# MCU.net
KiCad netlist of a schematic drawn in Altium Designer
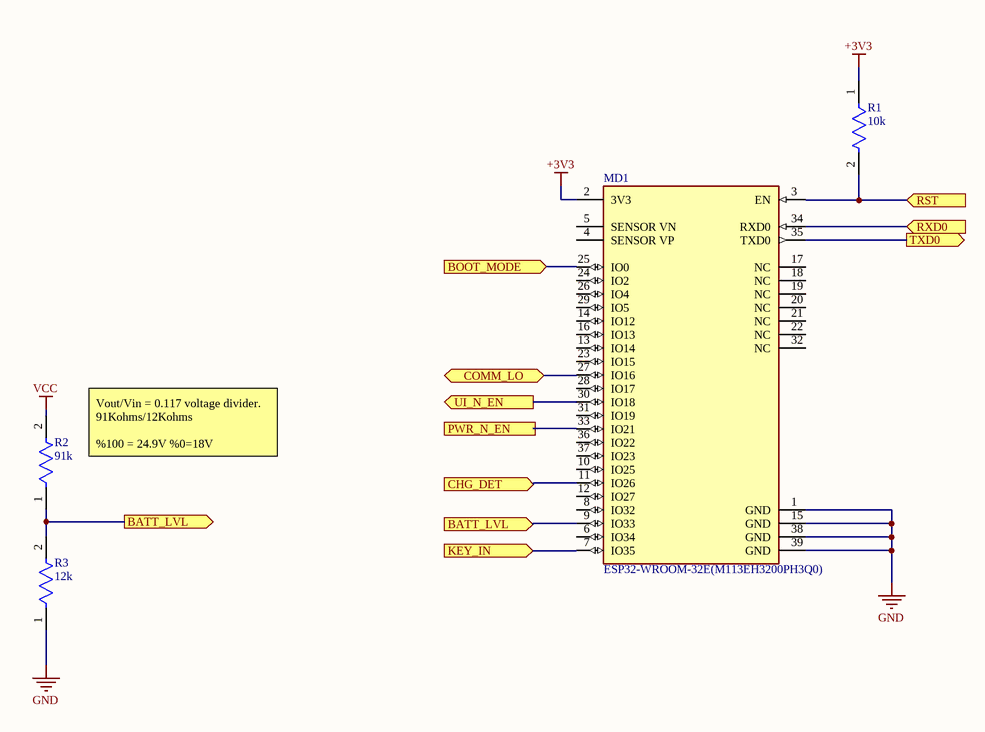
[diagram p0: MCU.SchDoc]

(export (version "E")
  (design (tool "Eeschema 10.0.6"))
  (components
    (comp (ref "MD1")
      (value "ESP32-WROOM-32E(M113EH3200PH3Q0)")
      (footprint "FP-ESP32-WROOM-32E_M113EH-MFG")
      (description "RX TXRX MOD WIFI TRACE ANT SMD")
      (fields (field (name "LCSC PART #") "C701341"))
      (libsource (lib "Altium Content Vault") (part "a4840fbd16b6d3d8633d6b8ddc62dfb"))
    )
    (comp (ref "R1")
      (value "10k")
      (footprint "FP-RP731J-MFG")
      (fields
        (field (name "MANUFACTURER") "TE Connectivity")
        (field (name "OCTOPART") "https://octopart.com/rp73d1j8r45btdg-te+connectivity-42630912")
        (field (name "MANUFACTURER PART NUMBER") "RP73D1J8R45BTDG")
      )
      (libsource (lib "Altium Content Vault") (part "1029c3af85768c4190bb7ad29bc67b5"))
    )
    (comp (ref "R2")
      (value "91k")
      (footprint "FP-RP731J-MFG")
      (fields
        (field (name "MANUFACTURER") "TE Connectivity")
        (field (name "OCTOPART") "https://octopart.com/rp73d1j8r45btdg-te+connectivity-42630912")
        (field (name "MANUFACTURER PART NUMBER") "RP73D1J8R45BTDG")
      )
      (libsource (lib "Altium Content Vault") (part "1029c3af85768c4190bb7ad29bc67b5"))
    )
    (comp (ref "R3")
      (value "12k")
      (footprint "FP-RP731J-MFG")
      (fields
        (field (name "MANUFACTURER") "TE Connectivity")
        (field (name "OCTOPART") "https://octopart.com/rp73d1j8r45btdg-te+connectivity-42630912")
        (field (name "MANUFACTURER PART NUMBER") "RP73D1J8R45BTDG")
      )
      (libsource (lib "Altium Content Vault") (part "1029c3af85768c4190bb7ad29bc67b5"))
    )
  )
  (nets
    (net (code "1") (name "+3V3") (class "Default")
      (node (ref "MD1") (pin "2") (pinfunction "3V3_2") (pintype "power_in"))
      (node (ref "R1") (pin "1") (pinfunction "1_1") (pintype "passive"))
    )
    (net (code "2") (name "/BATT_LVL") (class "Default")
      (node (ref "MD1") (pin "9") (pinfunction "IO33_9") (pintype "bidirectional"))
      (node (ref "R2") (pin "1") (pinfunction "1_1") (pintype "passive"))
      (node (ref "R3") (pin "2") (pinfunction "2_2") (pintype "passive"))
    )
    (net (code "3") (name "/BOOT_MODE") (class "Default")
      (node (ref "MD1") (pin "25") (pinfunction "IO0_25") (pintype "bidirectional"))
    )
    (net (code "4") (name "/CHG_DET") (class "Default")
      (node (ref "MD1") (pin "11") (pinfunction "IO26_11") (pintype "bidirectional"))
    )
    (net (code "5") (name "/COMM_LO") (class "Default")
      (node (ref "MD1") (pin "27") (pinfunction "IO16_27") (pintype "bidirectional"))
    )
    (net (code "6") (name "/KEY_IN") (class "Default")
      (node (ref "MD1") (pin "7") (pinfunction "IO35_7") (pintype "bidirectional"))
    )
    (net (code "7") (name "/PWR_N_EN") (class "Default")
      (node (ref "MD1") (pin "33") (pinfunction "IO21_33") (pintype "bidirectional"))
    )
    (net (code "8") (name "/RST") (class "Default")
      (node (ref "MD1") (pin "3") (pinfunction "EN_3") (pintype "input"))
      (node (ref "R1") (pin "2") (pinfunction "2_2") (pintype "passive"))
    )
    (net (code "9") (name "/RXD0") (class "Default")
      (node (ref "MD1") (pin "34") (pinfunction "RXD0_34") (pintype "input"))
    )
    (net (code "10") (name "/TXD0") (class "Default")
      (node (ref "MD1") (pin "35") (pinfunction "TXD0_35") (pintype "output"))
    )
    (net (code "11") (name "/UI_N_EN") (class "Default")
      (node (ref "MD1") (pin "30") (pinfunction "IO18_30") (pintype "bidirectional"))
    )
    (net (code "12") (name "GND") (class "Default")
      (node (ref "MD1") (pin "1") (pinfunction "GND_1") (pintype "power_in"))
      (node (ref "MD1") (pin "15") (pinfunction "GND_15") (pintype "power_in"))
      (node (ref "MD1") (pin "38") (pinfunction "GND_38") (pintype "power_in"))
      (node (ref "MD1") (pin "39") (pinfunction "GND_39") (pintype "power_in"))
      (node (ref "R3") (pin "1") (pinfunction "1_1") (pintype "passive"))
    )
    (net (code "13") (name "VCC") (class "Default")
      (node (ref "R2") (pin "2") (pinfunction "2_2") (pintype "passive"))
    )
    (net (code "14") (name "unconnected-(MD1-IO2-Pad24)") (class "Default")
      (node (ref "MD1") (pin "24") (pinfunction "IO2_24") (pintype "bidirectional"))
    )
    (net (code "15") (name "unconnected-(MD1-IO4-Pad26)") (class "Default")
      (node (ref "MD1") (pin "26") (pinfunction "IO4_26") (pintype "bidirectional"))
    )
    (net (code "16") (name "unconnected-(MD1-IO5-Pad29)") (class "Default")
      (node (ref "MD1") (pin "29") (pinfunction "IO5_29") (pintype "bidirectional"))
    )
    (net (code "17") (name "unconnected-(MD1-IO12-Pad14)") (class "Default")
      (node (ref "MD1") (pin "14") (pinfunction "IO12_14") (pintype "bidirectional"))
    )
    (net (code "18") (name "unconnected-(MD1-IO13-Pad16)") (class "Default")
      (node (ref "MD1") (pin "16") (pinfunction "IO13_16") (pintype "bidirectional"))
    )
    (net (code "19") (name "unconnected-(MD1-IO14-Pad13)") (class "Default")
      (node (ref "MD1") (pin "13") (pinfunction "IO14_13") (pintype "bidirectional"))
    )
    (net (code "20") (name "unconnected-(MD1-IO15-Pad23)") (class "Default")
      (node (ref "MD1") (pin "23") (pinfunction "IO15_23") (pintype "bidirectional"))
    )
    (net (code "21") (name "unconnected-(MD1-IO17-Pad28)") (class "Default")
      (node (ref "MD1") (pin "28") (pinfunction "IO17_28") (pintype "bidirectional"))
    )
    (net (code "22") (name "unconnected-(MD1-IO19-Pad31)") (class "Default")
      (node (ref "MD1") (pin "31") (pinfunction "IO19_31") (pintype "bidirectional"))
    )
    (net (code "23") (name "unconnected-(MD1-IO22-Pad36)") (class "Default")
      (node (ref "MD1") (pin "36") (pinfunction "IO22_36") (pintype "bidirectional"))
    )
    (net (code "24") (name "unconnected-(MD1-IO23-Pad37)") (class "Default")
      (node (ref "MD1") (pin "37") (pinfunction "IO23_37") (pintype "bidirectional"))
    )
    (net (code "25") (name "unconnected-(MD1-IO25-Pad10)") (class "Default")
      (node (ref "MD1") (pin "10") (pinfunction "IO25_10") (pintype "bidirectional"))
    )
    (net (code "26") (name "unconnected-(MD1-IO27-Pad12)") (class "Default")
      (node (ref "MD1") (pin "12") (pinfunction "IO27_12") (pintype "bidirectional"))
    )
    (net (code "27") (name "unconnected-(MD1-IO32-Pad8)") (class "Default")
      (node (ref "MD1") (pin "8") (pinfunction "IO32_8") (pintype "bidirectional"))
    )
    (net (code "28") (name "unconnected-(MD1-IO34-Pad6)") (class "Default")
      (node (ref "MD1") (pin "6") (pinfunction "IO34_6") (pintype "bidirectional"))
    )
    (net (code "29") (name "unconnected-(MD1-NC-Pad17)") (class "Default")
      (node (ref "MD1") (pin "17") (pinfunction "NC_17") (pintype "passive"))
    )
    (net (code "30") (name "unconnected-(MD1-NC-Pad18)") (class "Default")
      (node (ref "MD1") (pin "18") (pinfunction "NC_18") (pintype "passive"))
    )
    (net (code "31") (name "unconnected-(MD1-NC-Pad19)") (class "Default")
      (node (ref "MD1") (pin "19") (pinfunction "NC_19") (pintype "passive"))
    )
    (net (code "32") (name "unconnected-(MD1-NC-Pad20)") (class "Default")
      (node (ref "MD1") (pin "20") (pinfunction "NC_20") (pintype "passive"))
    )
    (net (code "33") (name "unconnected-(MD1-NC-Pad21)") (class "Default")
      (node (ref "MD1") (pin "21") (pinfunction "NC_21") (pintype "passive"))
    )
    (net (code "34") (name "unconnected-(MD1-NC-Pad22)") (class "Default")
      (node (ref "MD1") (pin "22") (pinfunction "NC_22") (pintype "passive"))
    )
    (net (code "35") (name "unconnected-(MD1-NC-Pad32)") (class "Default")
      (node (ref "MD1") (pin "32") (pinfunction "NC_32") (pintype "passive"))
    )
    (net (code "36") (name "unconnected-(MD1-SENSOR_VN-Pad5)") (class "Default")
      (node (ref "MD1") (pin "5") (pinfunction "SENSOR_VN_5") (pintype "passive"))
    )
    (net (code "37") (name "unconnected-(MD1-SENSOR_VP-Pad4)") (class "Default")
      (node (ref "MD1") (pin "4") (pinfunction "SENSOR_VP_4") (pintype "passive"))
    )
  )
)
